# power-v2v5.net
KiCad netlist of a schematic drawn in Altium Designer
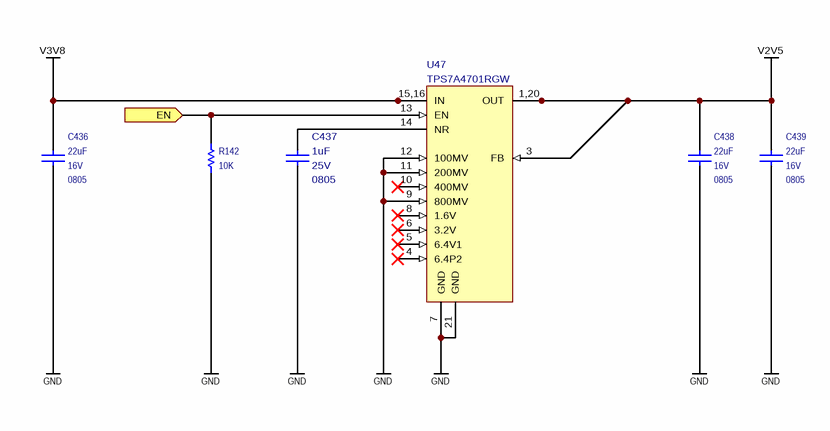
[diagram p0: power-v2v5.SchDoc]

(export (version "E")
  (design (tool "Eeschema 10.0.6"))
  (components
    (comp (ref "C436")
      (value "22uF")
      (footprint "generic:CAPC200X125X145L45N")
      (description "Ceramic Capacitor 22uF ±10% 16V X5R 0805")
      (fields
        (field (name "MANUFACTURER") "Samsung")
        (field (name "VOLTAGE") "16V")
        (field (name "PACKAGE") "0805")
        (field (name "TOLERANCE") "±10%")
      )
      (libsource (lib "generic") (part "CAP 0603"))
    )
    (comp (ref "C437")
      (value "1uF")
      (footprint "CAPC200X125X145L45N")
      (description "Ceramic Capacitor 1uF ±10% 25V X7R 0805")
      (fields
        (field (name "MANUFACTURER") "Taiyo Yuden")
        (field (name "TOLERANCE") "±10%")
        (field (name "PACKAGE") "0805")
        (field (name "VOLTAGE") "25V")
      )
      (libsource (lib "capacitors") (part "CAP"))
    )
    (comp (ref "C438")
      (value "22uF")
      (footprint "generic:CAPC200X125X145L45N")
      (description "Ceramic Capacitor 22uF ±10% 16V X5R 0805")
      (fields
        (field (name "MANUFACTURER") "Samsung")
        (field (name "VOLTAGE") "16V")
        (field (name "PACKAGE") "0805")
        (field (name "TOLERANCE") "±10%")
      )
      (libsource (lib "generic") (part "CAP 0603"))
    )
    (comp (ref "C439")
      (value "22uF")
      (footprint "generic:CAPC200X125X145L45N")
      (description "Ceramic Capacitor 22uF ±10% 16V X5R 0805")
      (fields
        (field (name "MANUFACTURER") "Samsung")
        (field (name "VOLTAGE") "16V")
        (field (name "PACKAGE") "0805")
        (field (name "TOLERANCE") "±10%")
      )
      (libsource (lib "generic") (part "CAP 0603"))
    )
    (comp (ref "R142")
      (value "10K")
      (footprint "generic:RESC1005X40N")
      (description "Thick Film Resistor 10k ±1% 0.1W 50V 0402")
      (fields (field (name "MANUFACTURER") "Panasonic") (field (name "TOLERANCE") "±1%"))
      (libsource (lib "Graviton") (part "RES 0402"))
    )
    (comp (ref "U47")
      (value "TPS7A4701RGW")
      (footprint "QFN65P500X500X100-21N")
      (description "Low-Dropout Linear Regulator 20-VQFN")
      (fields (field (name "MANUFACTURER") "Texas Instruments"))
      (libsource (lib "ti") (part "TPS7A4701RGW_1"))
    )
  )
  (nets
    (net (code "1") (name "/EN") (class "Default")
      (node (ref "R142") (pin "1") (pinfunction "1_1") (pintype "passive"))
      (node (ref "U47") (pin "13") (pinfunction "EN_13") (pintype "input"))
    )
    (net (code "2") (name "GND") (class "Default")
      (node (ref "C436") (pin "1") (pinfunction "1_1") (pintype "passive"))
      (node (ref "C437") (pin "2") (pinfunction "2_2") (pintype "passive"))
      (node (ref "C438") (pin "1") (pinfunction "1_1") (pintype "passive"))
      (node (ref "C439") (pin "1") (pinfunction "1_1") (pintype "passive"))
      (node (ref "R142") (pin "2") (pinfunction "2_2") (pintype "passive"))
      (node (ref "U47") (pin "11") (pinfunction "200MV_11") (pintype "input"))
      (node (ref "U47") (pin "12") (pinfunction "100MV_12") (pintype "input"))
      (node (ref "U47") (pin "21") (pinfunction "GND_21") (pintype "power_in"))
      (node (ref "U47") (pin "7") (pinfunction "GND_7") (pintype "power_in"))
      (node (ref "U47") (pin "9") (pinfunction "800MV_9") (pintype "input"))
    )
    (net (code "3") (name "Net-(U47-NR)") (class "Default")
      (node (ref "C437") (pin "1") (pinfunction "1_1") (pintype "passive"))
      (node (ref "U47") (pin "14") (pinfunction "NR_14") (pintype "passive"))
    )
    (net (code "4") (name "V2V5") (class "Default")
      (node (ref "C438") (pin "2") (pinfunction "2_2") (pintype "passive"))
      (node (ref "C439") (pin "2") (pinfunction "2_2") (pintype "passive"))
      (node (ref "U47") (pin "1") (pinfunction "OUT_1") (pintype "passive"))
      (node (ref "U47") (pin "20") (pinfunction "OUT_20") (pintype "passive"))
      (node (ref "U47") (pin "3") (pinfunction "FB_3") (pintype "input"))
    )
    (net (code "5") (name "V3V8") (class "Default")
      (node (ref "C436") (pin "2") (pinfunction "2_2") (pintype "passive"))
      (node (ref "U47") (pin "15") (pinfunction "IN_15") (pintype "passive"))
      (node (ref "U47") (pin "16") (pinfunction "IN_16") (pintype "passive"))
    )
    (net (code "6") (name "unconnected-(U47-1.6V-Pad8)") (class "Default")
      (node (ref "U47") (pin "8") (pinfunction "1.6V_8") (pintype "input+no_connect"))
    )
    (net (code "7") (name "unconnected-(U47-3.2V-Pad6)") (class "Default")
      (node (ref "U47") (pin "6") (pinfunction "3.2V_6") (pintype "input+no_connect"))
    )
    (net (code "8") (name "unconnected-(U47-6.4P2-Pad4)") (class "Default")
      (node (ref "U47") (pin "4") (pinfunction "6.4P2_4") (pintype "input+no_connect"))
    )
    (net (code "9") (name "unconnected-(U47-6.4V1-Pad5)") (class "Default")
      (node (ref "U47") (pin "5") (pinfunction "6.4V1_5") (pintype "input+no_connect"))
    )
    (net (code "10") (name "unconnected-(U47-400MV-Pad10)") (class "Default")
      (node (ref "U47") (pin "10") (pinfunction "400MV_10") (pintype "input+no_connect"))
    )
  )
)
